# SSR_Board.net
KiCad netlist of a schematic drawn in EAGLE
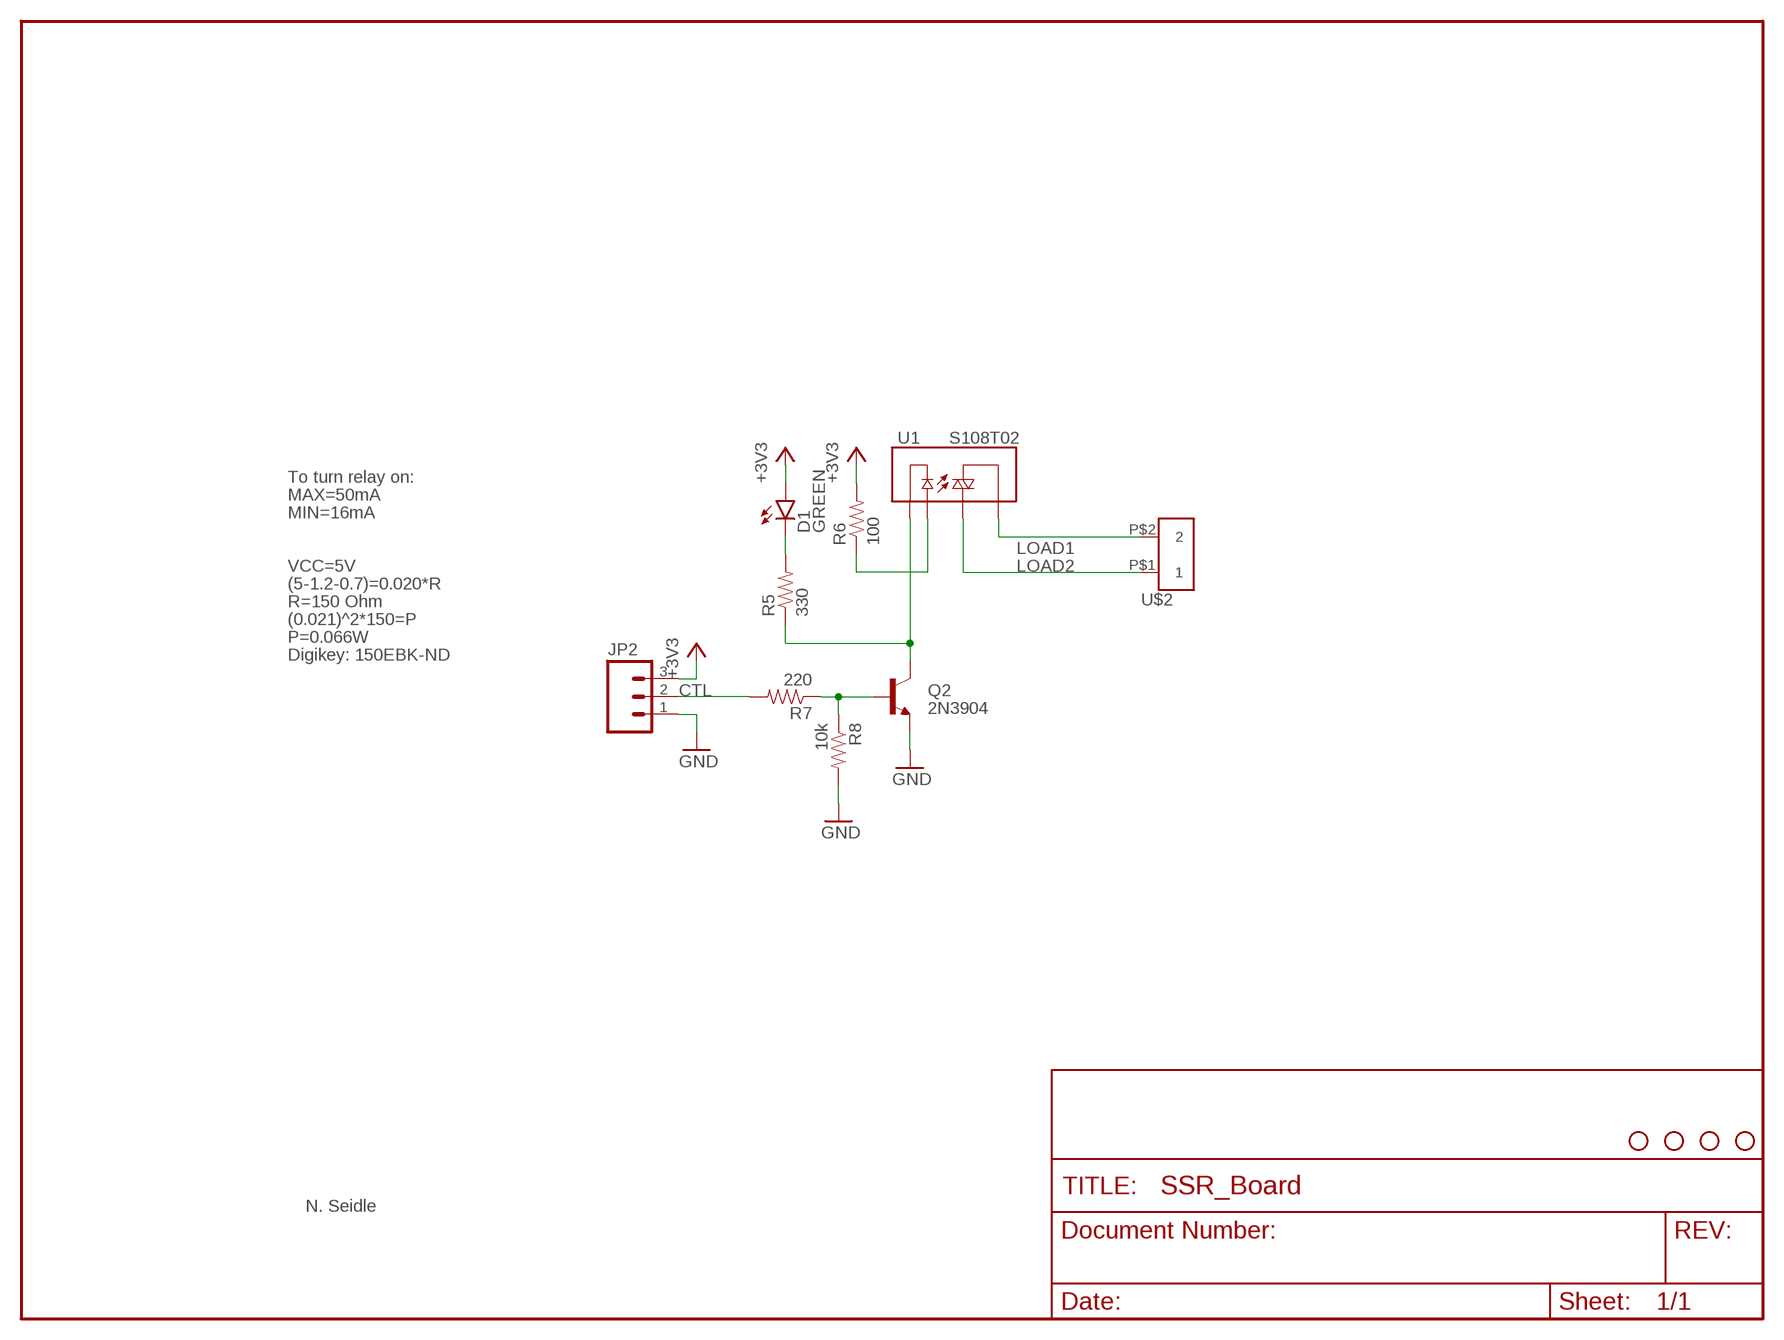
[diagram p0: schematic, sheet 1]

(export (version "E")
  (design (tool "Eeschema 10.0.6"))
  (components
    (comp (ref "D1")
      (value "GREEN")
      (footprint "eagle-import:LED-0603")
      (libsource (lib "eagle-import") (part "LED-GREEN0603"))
    )
    (comp (ref "JP2")
      (value "M03SCREW")
      (footprint "eagle-import:SCREWTERMINAL-3.5MM-3")
      (libsource (lib "eagle-import") (part "M03SCREW"))
    )
    (comp (ref "Q2")
      (value "2N3904")
      (footprint "eagle-import:SOT23-3")
      (libsource (lib "eagle-import") (part "TRANSISTOR_NPNSOT23-3"))
    )
    (comp (ref "R5")
      (value "330")
      (footprint "eagle-import:0603-RES")
      (libsource (lib "eagle-import") (part "RESISTOR0603-RES"))
    )
    (comp (ref "R6")
      (value "100")
      (footprint "eagle-import:0603-RES")
      (libsource (lib "eagle-import") (part "RESISTOR0603-RES"))
    )
    (comp (ref "R7")
      (value "220")
      (footprint "eagle-import:0603-RES")
      (libsource (lib "eagle-import") (part "RESISTOR0603-RES"))
    )
    (comp (ref "R8")
      (value "10k")
      (footprint "eagle-import:0603-RES")
      (libsource (lib "eagle-import") (part "RESISTOR0603-RES"))
    )
    (comp (ref "U$2")
      (value "6PCV-02-006")
      (footprint "eagle-import:6PCV-02-006")
      (libsource (lib "eagle-import") (part "6PCV-02-006"))
    )
    (comp (ref "U$3")
      (value "STAND-OFF")
      (footprint "eagle-import:STAND-OFF")
      (libsource (lib "eagle-import") (part "STAND-OFF"))
    )
    (comp (ref "U$4")
      (value "STAND-OFF")
      (footprint "eagle-import:STAND-OFF")
      (libsource (lib "eagle-import") (part "STAND-OFF"))
    )
    (comp (ref "U$5")
      (value "STAND-OFF")
      (footprint "eagle-import:STAND-OFF")
      (libsource (lib "eagle-import") (part "STAND-OFF"))
    )
    (comp (ref "U$7")
      (value "STAND-OFF")
      (footprint "eagle-import:STAND-OFF")
      (libsource (lib "eagle-import") (part "STAND-OFF"))
    )
    (comp (ref "U1")
      (value "S108T02")
      (footprint "eagle-import:RELAY-S108T02")
      (libsource (lib "eagle-import") (part "RELAY-SOLIDSTATEPTH"))
    )
  )
  (nets
    (net (code "1") (name "+3V3") (class "Default")
      (node (ref "D1") (pin "A") (pinfunction "A_A") (pintype "passive"))
      (node (ref "JP2") (pin "3") (pinfunction "3_3") (pintype "passive"))
      (node (ref "R6") (pin "2") (pinfunction "2_2") (pintype "passive"))
    )
    (net (code "2") (name "/CTL") (class "Default")
      (node (ref "JP2") (pin "2") (pinfunction "2_2") (pintype "passive"))
      (node (ref "R7") (pin "2") (pinfunction "2_2") (pintype "passive"))
    )
    (net (code "3") (name "/LOAD1") (class "Default")
      (node (ref "U$2") (pin "P$2") (pinfunction "2_P$2") (pintype "bidirectional"))
      (node (ref "U1") (pin "1") (pinfunction "T1_1") (pintype "bidirectional"))
    )
    (net (code "4") (name "/LOAD2") (class "Default")
      (node (ref "U$2") (pin "P$1") (pinfunction "1_P$1") (pintype "bidirectional"))
      (node (ref "U1") (pin "2") (pinfunction "T2_2") (pintype "bidirectional"))
    )
    (net (code "5") (name "GND") (class "Default")
      (node (ref "JP2") (pin "1") (pinfunction "1_1") (pintype "passive"))
      (node (ref "Q2") (pin "2") (pinfunction "E_2") (pintype "passive"))
      (node (ref "R8") (pin "2") (pinfunction "2_2") (pintype "passive"))
    )
    (net (code "6") (name "Net-(D1-PadC)") (class "Default")
      (node (ref "D1") (pin "C") (pinfunction "C_C") (pintype "passive"))
      (node (ref "R5") (pin "2") (pinfunction "2_2") (pintype "passive"))
    )
    (net (code "7") (name "Net-(Q2-B)") (class "Default")
      (node (ref "Q2") (pin "1") (pinfunction "B_1") (pintype "passive"))
      (node (ref "R7") (pin "1") (pinfunction "1_1") (pintype "passive"))
      (node (ref "R8") (pin "1") (pinfunction "1_1") (pintype "passive"))
    )
    (net (code "8") (name "Net-(Q2-C)") (class "Default")
      (node (ref "Q2") (pin "3") (pinfunction "C_3") (pintype "passive"))
      (node (ref "R5") (pin "1") (pinfunction "1_1") (pintype "passive"))
      (node (ref "U1") (pin "4") (pinfunction "-_4") (pintype "bidirectional"))
    )
    (net (code "9") (name "Net-(U1-+)") (class "Default")
      (node (ref "R6") (pin "1") (pinfunction "1_1") (pintype "passive"))
      (node (ref "U1") (pin "3") (pinfunction "+_3") (pintype "bidirectional"))
    )
  )
)
